# 05_LCD.net
KiCad netlist of a schematic drawn in Altium Designer
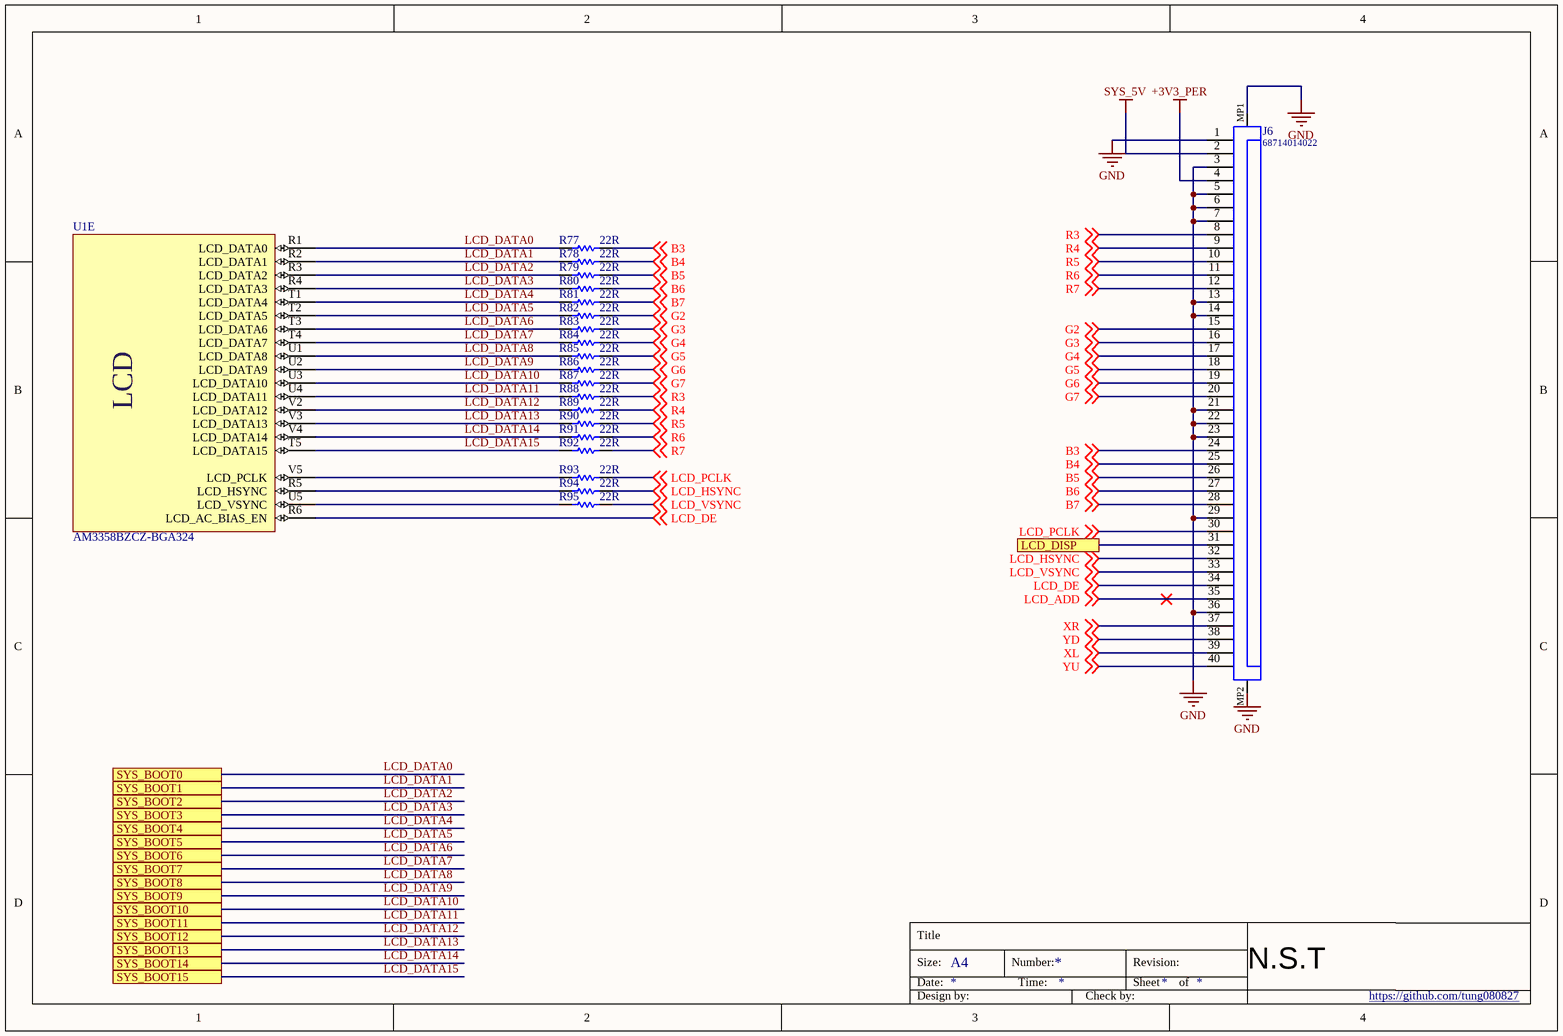
[diagram p0: 05. LCD.SchDoc]

(export (version "E")
  (design (tool "Eeschema 10.0.6"))
  (components
    (comp (ref "J6")
      (value "68714014022")
      (footprint "68714014022")
      (description "SMT ZIF Connectors WR-FPC, Horizontal, Top Contact, pitch 0.5 mm, 40 pins")
      (fields (field (name "MANUFACTURER") "Wurth Elektronik") (field (name "PUBLISHER") "WurthElektronik"))
      (libsource (lib "Altium Content Vault") (part "WE-6871401XXX22-40"))
    )
    (comp (ref "R77")
      (value "22R")
      (footprint "RESC1005X40X25LL05T05")
      (description "Chip Resistor, 22 Ohm, +/- 1%, 0.1 W, -55 to 155 degC, 0402 (1005 Metric), RoHS, Tape and Reel")
      (fields (field (name "PARTNUMBER") "ERJ-2RKF22R0X") (field (name "TOLERANCE") "1%"))
      (libsource (lib "AM3358_DEV_BOARD") (part "RES-2"))
    )
    (comp (ref "R78")
      (value "22R")
      (footprint "RESC1005X40X25LL05T05")
      (description "Chip Resistor, 22 Ohm, +/- 1%, 0.1 W, -55 to 155 degC, 0402 (1005 Metric), RoHS, Tape and Reel")
      (fields (field (name "PARTNUMBER") "ERJ-2RKF22R0X") (field (name "TOLERANCE") "1%"))
      (libsource (lib "AM3358_DEV_BOARD") (part "RES-2"))
    )
    (comp (ref "R79")
      (value "22R")
      (footprint "RESC1005X40X25LL05T05")
      (description "Chip Resistor, 22 Ohm, +/- 1%, 0.1 W, -55 to 155 degC, 0402 (1005 Metric), RoHS, Tape and Reel")
      (fields (field (name "PARTNUMBER") "ERJ-2RKF22R0X") (field (name "TOLERANCE") "1%"))
      (libsource (lib "AM3358_DEV_BOARD") (part "RES-2"))
    )
    (comp (ref "R80")
      (value "22R")
      (footprint "RESC1005X40X25LL05T05")
      (description "Chip Resistor, 22 Ohm, +/- 1%, 0.1 W, -55 to 155 degC, 0402 (1005 Metric), RoHS, Tape and Reel")
      (fields (field (name "PARTNUMBER") "ERJ-2RKF22R0X") (field (name "TOLERANCE") "1%"))
      (libsource (lib "AM3358_DEV_BOARD") (part "RES-2"))
    )
    (comp (ref "R81")
      (value "22R")
      (footprint "RESC1005X40X25LL05T05")
      (description "Chip Resistor, 22 Ohm, +/- 1%, 0.1 W, -55 to 155 degC, 0402 (1005 Metric), RoHS, Tape and Reel")
      (fields (field (name "PARTNUMBER") "ERJ-2RKF22R0X") (field (name "TOLERANCE") "1%"))
      (libsource (lib "AM3358_DEV_BOARD") (part "RES-2"))
    )
    (comp (ref "R82")
      (value "22R")
      (footprint "RESC1005X40X25LL05T05")
      (description "Chip Resistor, 22 Ohm, +/- 1%, 0.1 W, -55 to 155 degC, 0402 (1005 Metric), RoHS, Tape and Reel")
      (fields (field (name "PARTNUMBER") "ERJ-2RKF22R0X") (field (name "TOLERANCE") "1%"))
      (libsource (lib "AM3358_DEV_BOARD") (part "RES-2"))
    )
    (comp (ref "R83")
      (value "22R")
      (footprint "RESC1005X40X25LL05T05")
      (description "Chip Resistor, 22 Ohm, +/- 1%, 0.1 W, -55 to 155 degC, 0402 (1005 Metric), RoHS, Tape and Reel")
      (fields (field (name "PARTNUMBER") "ERJ-2RKF22R0X") (field (name "TOLERANCE") "1%"))
      (libsource (lib "AM3358_DEV_BOARD") (part "RES-2"))
    )
    (comp (ref "R84")
      (value "22R")
      (footprint "RESC1005X40X25LL05T05")
      (description "Chip Resistor, 22 Ohm, +/- 1%, 0.1 W, -55 to 155 degC, 0402 (1005 Metric), RoHS, Tape and Reel")
      (fields (field (name "PARTNUMBER") "ERJ-2RKF22R0X") (field (name "TOLERANCE") "1%"))
      (libsource (lib "AM3358_DEV_BOARD") (part "RES-2"))
    )
    (comp (ref "R85")
      (value "22R")
      (footprint "RESC1005X40X25LL05T05")
      (description "Chip Resistor, 22 Ohm, +/- 1%, 0.1 W, -55 to 155 degC, 0402 (1005 Metric), RoHS, Tape and Reel")
      (fields (field (name "PARTNUMBER") "ERJ-2RKF22R0X") (field (name "TOLERANCE") "1%"))
      (libsource (lib "AM3358_DEV_BOARD") (part "RES-2"))
    )
    (comp (ref "R86")
      (value "22R")
      (footprint "RESC1005X40X25LL05T05")
      (description "Chip Resistor, 22 Ohm, +/- 1%, 0.1 W, -55 to 155 degC, 0402 (1005 Metric), RoHS, Tape and Reel")
      (fields (field (name "PARTNUMBER") "ERJ-2RKF22R0X") (field (name "TOLERANCE") "1%"))
      (libsource (lib "AM3358_DEV_BOARD") (part "RES-2"))
    )
    (comp (ref "R87")
      (value "22R")
      (footprint "RESC1005X40X25LL05T05")
      (description "Chip Resistor, 22 Ohm, +/- 1%, 0.1 W, -55 to 155 degC, 0402 (1005 Metric), RoHS, Tape and Reel")
      (fields (field (name "PARTNUMBER") "ERJ-2RKF22R0X") (field (name "TOLERANCE") "1%"))
      (libsource (lib "AM3358_DEV_BOARD") (part "RES-2"))
    )
    (comp (ref "R88")
      (value "22R")
      (footprint "RESC1005X40X25LL05T05")
      (description "Chip Resistor, 22 Ohm, +/- 1%, 0.1 W, -55 to 155 degC, 0402 (1005 Metric), RoHS, Tape and Reel")
      (fields (field (name "PARTNUMBER") "ERJ-2RKF22R0X") (field (name "TOLERANCE") "1%"))
      (libsource (lib "AM3358_DEV_BOARD") (part "RES-2"))
    )
    (comp (ref "R89")
      (value "22R")
      (footprint "RESC1005X40X25LL05T05")
      (description "Chip Resistor, 22 Ohm, +/- 1%, 0.1 W, -55 to 155 degC, 0402 (1005 Metric), RoHS, Tape and Reel")
      (fields (field (name "PARTNUMBER") "ERJ-2RKF22R0X") (field (name "TOLERANCE") "1%"))
      (libsource (lib "AM3358_DEV_BOARD") (part "RES-2"))
    )
    (comp (ref "R90")
      (value "22R")
      (footprint "RESC1005X40X25LL05T05")
      (description "Chip Resistor, 22 Ohm, +/- 1%, 0.1 W, -55 to 155 degC, 0402 (1005 Metric), RoHS, Tape and Reel")
      (fields (field (name "PARTNUMBER") "ERJ-2RKF22R0X") (field (name "TOLERANCE") "1%"))
      (libsource (lib "AM3358_DEV_BOARD") (part "RES-2"))
    )
    (comp (ref "R91")
      (value "22R")
      (footprint "RESC1005X40X25LL05T05")
      (description "Chip Resistor, 22 Ohm, +/- 1%, 0.1 W, -55 to 155 degC, 0402 (1005 Metric), RoHS, Tape and Reel")
      (fields (field (name "PARTNUMBER") "ERJ-2RKF22R0X") (field (name "TOLERANCE") "1%"))
      (libsource (lib "AM3358_DEV_BOARD") (part "RES-2"))
    )
    (comp (ref "R92")
      (value "22R")
      (footprint "RESC1005X40X25LL05T05")
      (description "Chip Resistor, 22 Ohm, +/- 1%, 0.1 W, -55 to 155 degC, 0402 (1005 Metric), RoHS, Tape and Reel")
      (fields (field (name "PARTNUMBER") "ERJ-2RKF22R0X") (field (name "TOLERANCE") "1%"))
      (libsource (lib "AM3358_DEV_BOARD") (part "RES-2"))
    )
    (comp (ref "R93")
      (value "22R")
      (footprint "RESC1005X40X25LL05T05")
      (description "Chip Resistor, 22 Ohm, +/- 1%, 0.1 W, -55 to 155 degC, 0402 (1005 Metric), RoHS, Tape and Reel")
      (fields (field (name "PARTNUMBER") "ERJ-2RKF22R0X") (field (name "TOLERANCE") "1%"))
      (libsource (lib "AM3358_DEV_BOARD") (part "RES-2"))
    )
    (comp (ref "R94")
      (value "22R")
      (footprint "RESC1005X40X25LL05T05")
      (description "Chip Resistor, 22 Ohm, +/- 1%, 0.1 W, -55 to 155 degC, 0402 (1005 Metric), RoHS, Tape and Reel")
      (fields (field (name "PARTNUMBER") "ERJ-2RKF22R0X") (field (name "TOLERANCE") "1%"))
      (libsource (lib "AM3358_DEV_BOARD") (part "RES-2"))
    )
    (comp (ref "R95")
      (value "22R")
      (footprint "RESC1005X40X25LL05T05")
      (description "Chip Resistor, 22 Ohm, +/- 1%, 0.1 W, -55 to 155 degC, 0402 (1005 Metric), RoHS, Tape and Reel")
      (fields (field (name "PARTNUMBER") "ERJ-2RKF22R0X") (field (name "TOLERANCE") "1%"))
      (libsource (lib "AM3358_DEV_BOARD") (part "RES-2"))
    )
    (comp (ref "U1")
      (value "AM3358BZCZ-BGA324")
      (footprint "TI-ZCZ324")
      (libsource (lib "SyTungNguyen") (part "AM3358BZCZ100"))
    )
  )
  (nets
    (net (code "1") (name "+3V3_PER") (class "Default")
      (node (ref "J6") (pin "4") (pinfunction "4_4") (pintype "passive"))
    )
    (net (code "2") (name "/LCD_DATA0") (class "Default")
      (node (ref "R77") (pin "1") (pinfunction "1_1") (pintype "passive"))
      (node (ref "U1") (pin "R1") (pinfunction "LCD_DATA0_R1") (pintype "bidirectional"))
    )
    (net (code "3") (name "/LCD_DATA1") (class "Default")
      (node (ref "R78") (pin "1") (pinfunction "1_1") (pintype "passive"))
      (node (ref "U1") (pin "R2") (pinfunction "LCD_DATA1_R2") (pintype "bidirectional"))
    )
    (net (code "4") (name "/LCD_DATA2") (class "Default")
      (node (ref "R79") (pin "1") (pinfunction "1_1") (pintype "passive"))
      (node (ref "U1") (pin "R3") (pinfunction "LCD_DATA2_R3") (pintype "bidirectional"))
    )
    (net (code "5") (name "/LCD_DATA3") (class "Default")
      (node (ref "R80") (pin "1") (pinfunction "1_1") (pintype "passive"))
      (node (ref "U1") (pin "R4") (pinfunction "LCD_DATA3_R4") (pintype "bidirectional"))
    )
    (net (code "6") (name "/LCD_DATA4") (class "Default")
      (node (ref "R81") (pin "1") (pinfunction "1_1") (pintype "passive"))
      (node (ref "U1") (pin "T1") (pinfunction "LCD_DATA4_T1") (pintype "bidirectional"))
    )
    (net (code "7") (name "/LCD_DATA5") (class "Default")
      (node (ref "R82") (pin "1") (pinfunction "1_1") (pintype "passive"))
      (node (ref "U1") (pin "T2") (pinfunction "LCD_DATA5_T2") (pintype "bidirectional"))
    )
    (net (code "8") (name "/LCD_DATA6") (class "Default")
      (node (ref "R83") (pin "1") (pinfunction "1_1") (pintype "passive"))
      (node (ref "U1") (pin "T3") (pinfunction "LCD_DATA6_T3") (pintype "bidirectional"))
    )
    (net (code "9") (name "/LCD_DATA7") (class "Default")
      (node (ref "R84") (pin "1") (pinfunction "1_1") (pintype "passive"))
      (node (ref "U1") (pin "T4") (pinfunction "LCD_DATA7_T4") (pintype "bidirectional"))
    )
    (net (code "10") (name "/LCD_DATA8") (class "Default")
      (node (ref "R85") (pin "1") (pinfunction "1_1") (pintype "passive"))
      (node (ref "U1") (pin "U1") (pinfunction "LCD_DATA8_U1") (pintype "bidirectional"))
    )
    (net (code "11") (name "/LCD_DATA9") (class "Default")
      (node (ref "R86") (pin "1") (pinfunction "1_1") (pintype "passive"))
      (node (ref "U1") (pin "U2") (pinfunction "LCD_DATA9_U2") (pintype "bidirectional"))
    )
    (net (code "12") (name "/LCD_DATA10") (class "Default")
      (node (ref "R87") (pin "1") (pinfunction "1_1") (pintype "passive"))
      (node (ref "U1") (pin "U3") (pinfunction "LCD_DATA10_U3") (pintype "bidirectional"))
    )
    (net (code "13") (name "/LCD_DATA11") (class "Default")
      (node (ref "R88") (pin "1") (pinfunction "1_1") (pintype "passive"))
      (node (ref "U1") (pin "U4") (pinfunction "LCD_DATA11_U4") (pintype "bidirectional"))
    )
    (net (code "14") (name "/LCD_DATA12") (class "Default")
      (node (ref "R89") (pin "1") (pinfunction "1_1") (pintype "passive"))
      (node (ref "U1") (pin "V2") (pinfunction "LCD_DATA12_V2") (pintype "bidirectional"))
    )
    (net (code "15") (name "/LCD_DATA13") (class "Default")
      (node (ref "R90") (pin "1") (pinfunction "1_1") (pintype "passive"))
      (node (ref "U1") (pin "V3") (pinfunction "LCD_DATA13_V3") (pintype "bidirectional"))
    )
    (net (code "16") (name "/LCD_DATA14") (class "Default")
      (node (ref "R91") (pin "1") (pinfunction "1_1") (pintype "passive"))
      (node (ref "U1") (pin "V4") (pinfunction "LCD_DATA14_V4") (pintype "bidirectional"))
    )
    (net (code "17") (name "/LCD_DATA15") (class "Default")
      (node (ref "R92") (pin "1") (pinfunction "1_1") (pintype "passive"))
      (node (ref "U1") (pin "T5") (pinfunction "LCD_DATA15_T5") (pintype "bidirectional"))
    )
    (net (code "18") (name "/LCD_DISP") (class "Default")
      (node (ref "J6") (pin "31") (pinfunction "31_31") (pintype "passive"))
    )
    (net (code "19") (name "B3") (class "Default")
      (node (ref "J6") (pin "24") (pinfunction "24_24") (pintype "passive"))
      (node (ref "R77") (pin "2") (pinfunction "2_2") (pintype "passive"))
    )
    (net (code "20") (name "B4") (class "Default")
      (node (ref "J6") (pin "25") (pinfunction "25_25") (pintype "passive"))
      (node (ref "R78") (pin "2") (pinfunction "2_2") (pintype "passive"))
    )
    (net (code "21") (name "B5") (class "Default")
      (node (ref "J6") (pin "26") (pinfunction "26_26") (pintype "passive"))
      (node (ref "R79") (pin "2") (pinfunction "2_2") (pintype "passive"))
    )
    (net (code "22") (name "B6") (class "Default")
      (node (ref "J6") (pin "27") (pinfunction "27_27") (pintype "passive"))
      (node (ref "R80") (pin "2") (pinfunction "2_2") (pintype "passive"))
    )
    (net (code "23") (name "B7") (class "Default")
      (node (ref "J6") (pin "28") (pinfunction "28_28") (pintype "passive"))
      (node (ref "R81") (pin "2") (pinfunction "2_2") (pintype "passive"))
    )
    (net (code "24") (name "G2") (class "Default")
      (node (ref "J6") (pin "15") (pinfunction "15_15") (pintype "passive"))
      (node (ref "R82") (pin "2") (pinfunction "2_2") (pintype "passive"))
    )
    (net (code "25") (name "G3") (class "Default")
      (node (ref "J6") (pin "16") (pinfunction "16_16") (pintype "passive"))
      (node (ref "R83") (pin "2") (pinfunction "2_2") (pintype "passive"))
    )
    (net (code "26") (name "G4") (class "Default")
      (node (ref "J6") (pin "17") (pinfunction "17_17") (pintype "passive"))
      (node (ref "R84") (pin "2") (pinfunction "2_2") (pintype "passive"))
    )
    (net (code "27") (name "G5") (class "Default")
      (node (ref "J6") (pin "18") (pinfunction "18_18") (pintype "passive"))
      (node (ref "R85") (pin "2") (pinfunction "2_2") (pintype "passive"))
    )
    (net (code "28") (name "G6") (class "Default")
      (node (ref "J6") (pin "19") (pinfunction "19_19") (pintype "passive"))
      (node (ref "R86") (pin "2") (pinfunction "2_2") (pintype "passive"))
    )
    (net (code "29") (name "G7") (class "Default")
      (node (ref "J6") (pin "20") (pinfunction "20_20") (pintype "passive"))
      (node (ref "R87") (pin "2") (pinfunction "2_2") (pintype "passive"))
    )
    (net (code "30") (name "GND") (class "Default")
      (node (ref "J6") (pin "1") (pinfunction "1_1") (pintype "passive"))
      (node (ref "J6") (pin "13") (pinfunction "13_13") (pintype "passive"))
      (node (ref "J6") (pin "14") (pinfunction "14_14") (pintype "passive"))
      (node (ref "J6") (pin "21") (pinfunction "21_21") (pintype "passive"))
      (node (ref "J6") (pin "22") (pinfunction "22_22") (pintype "passive"))
      (node (ref "J6") (pin "23") (pinfunction "23_23") (pintype "passive"))
      (node (ref "J6") (pin "29") (pinfunction "29_29") (pintype "passive"))
      (node (ref "J6") (pin "3") (pinfunction "3_3") (pintype "passive"))
      (node (ref "J6") (pin "36") (pinfunction "36_36") (pintype "passive"))
      (node (ref "J6") (pin "5") (pinfunction "5_5") (pintype "passive"))
      (node (ref "J6") (pin "6") (pinfunction "6_6") (pintype "passive"))
      (node (ref "J6") (pin "7") (pinfunction "7_7") (pintype "passive"))
      (node (ref "J6") (pin "MP1") (pinfunction "MP1_MP1") (pintype "passive"))
      (node (ref "J6") (pin "MP2") (pinfunction "MP2_MP2") (pintype "passive"))
    )
    (net (code "31") (name "LCD_ADD") (class "Default")
      (node (ref "J6") (pin "35") (pinfunction "35_35") (pintype "passive"))
    )
    (net (code "32") (name "LCD_DE") (class "Default")
      (node (ref "J6") (pin "34") (pinfunction "34_34") (pintype "passive"))
      (node (ref "U1") (pin "R6") (pinfunction "LCD_AC_BIAS_EN_R6") (pintype "bidirectional"))
    )
    (net (code "33") (name "LCD_HSYNC") (class "Default")
      (node (ref "J6") (pin "32") (pinfunction "32_32") (pintype "passive"))
      (node (ref "R94") (pin "2") (pinfunction "2_2") (pintype "passive"))
    )
    (net (code "34") (name "LCD_PCLK") (class "Default")
      (node (ref "J6") (pin "30") (pinfunction "30_30") (pintype "passive"))
      (node (ref "R93") (pin "2") (pinfunction "2_2") (pintype "passive"))
    )
    (net (code "35") (name "LCD_VSYNC") (class "Default")
      (node (ref "J6") (pin "33") (pinfunction "33_33") (pintype "passive"))
      (node (ref "R95") (pin "2") (pinfunction "2_2") (pintype "passive"))
    )
    (net (code "36") (name "Net-(U1E-LCD_HSYNC)") (class "Default")
      (node (ref "R94") (pin "1") (pinfunction "1_1") (pintype "passive"))
      (node (ref "U1") (pin "R5") (pinfunction "LCD_HSYNC_R5") (pintype "bidirectional"))
    )
    (net (code "37") (name "Net-(U1E-LCD_PCLK)") (class "Default")
      (node (ref "R93") (pin "1") (pinfunction "1_1") (pintype "passive"))
      (node (ref "U1") (pin "V5") (pinfunction "LCD_PCLK_V5") (pintype "bidirectional"))
    )
    (net (code "38") (name "Net-(U1E-LCD_VSYNC)") (class "Default")
      (node (ref "R95") (pin "1") (pinfunction "1_1") (pintype "passive"))
      (node (ref "U1") (pin "U5") (pinfunction "LCD_VSYNC_U5") (pintype "bidirectional"))
    )
    (net (code "39") (name "R3") (class "Default")
      (node (ref "J6") (pin "8") (pinfunction "8_8") (pintype "passive"))
      (node (ref "R88") (pin "2") (pinfunction "2_2") (pintype "passive"))
    )
    (net (code "40") (name "R4") (class "Default")
      (node (ref "J6") (pin "9") (pinfunction "9_9") (pintype "passive"))
      (node (ref "R89") (pin "2") (pinfunction "2_2") (pintype "passive"))
    )
    (net (code "41") (name "R5") (class "Default")
      (node (ref "J6") (pin "10") (pinfunction "10_10") (pintype "passive"))
      (node (ref "R90") (pin "2") (pinfunction "2_2") (pintype "passive"))
    )
    (net (code "42") (name "R6") (class "Default")
      (node (ref "J6") (pin "11") (pinfunction "11_11") (pintype "passive"))
      (node (ref "R91") (pin "2") (pinfunction "2_2") (pintype "passive"))
    )
    (net (code "43") (name "R7") (class "Default")
      (node (ref "J6") (pin "12") (pinfunction "12_12") (pintype "passive"))
      (node (ref "R92") (pin "2") (pinfunction "2_2") (pintype "passive"))
    )
    (net (code "44") (name "SYS_5V") (class "Default")
      (node (ref "J6") (pin "2") (pinfunction "2_2") (pintype "passive"))
    )
    (net (code "45") (name "XL") (class "Default")
      (node (ref "J6") (pin "39") (pinfunction "39_39") (pintype "passive"))
    )
    (net (code "46") (name "XR") (class "Default")
      (node (ref "J6") (pin "37") (pinfunction "37_37") (pintype "passive"))
    )
    (net (code "47") (name "YD") (class "Default")
      (node (ref "J6") (pin "38") (pinfunction "38_38") (pintype "passive"))
    )
    (net (code "48") (name "YU") (class "Default")
      (node (ref "J6") (pin "40") (pinfunction "40_40") (pintype "passive"))
    )
  )
)
